# uart-opto-isolation.net
KiCad netlist of a schematic drawn in EAGLE
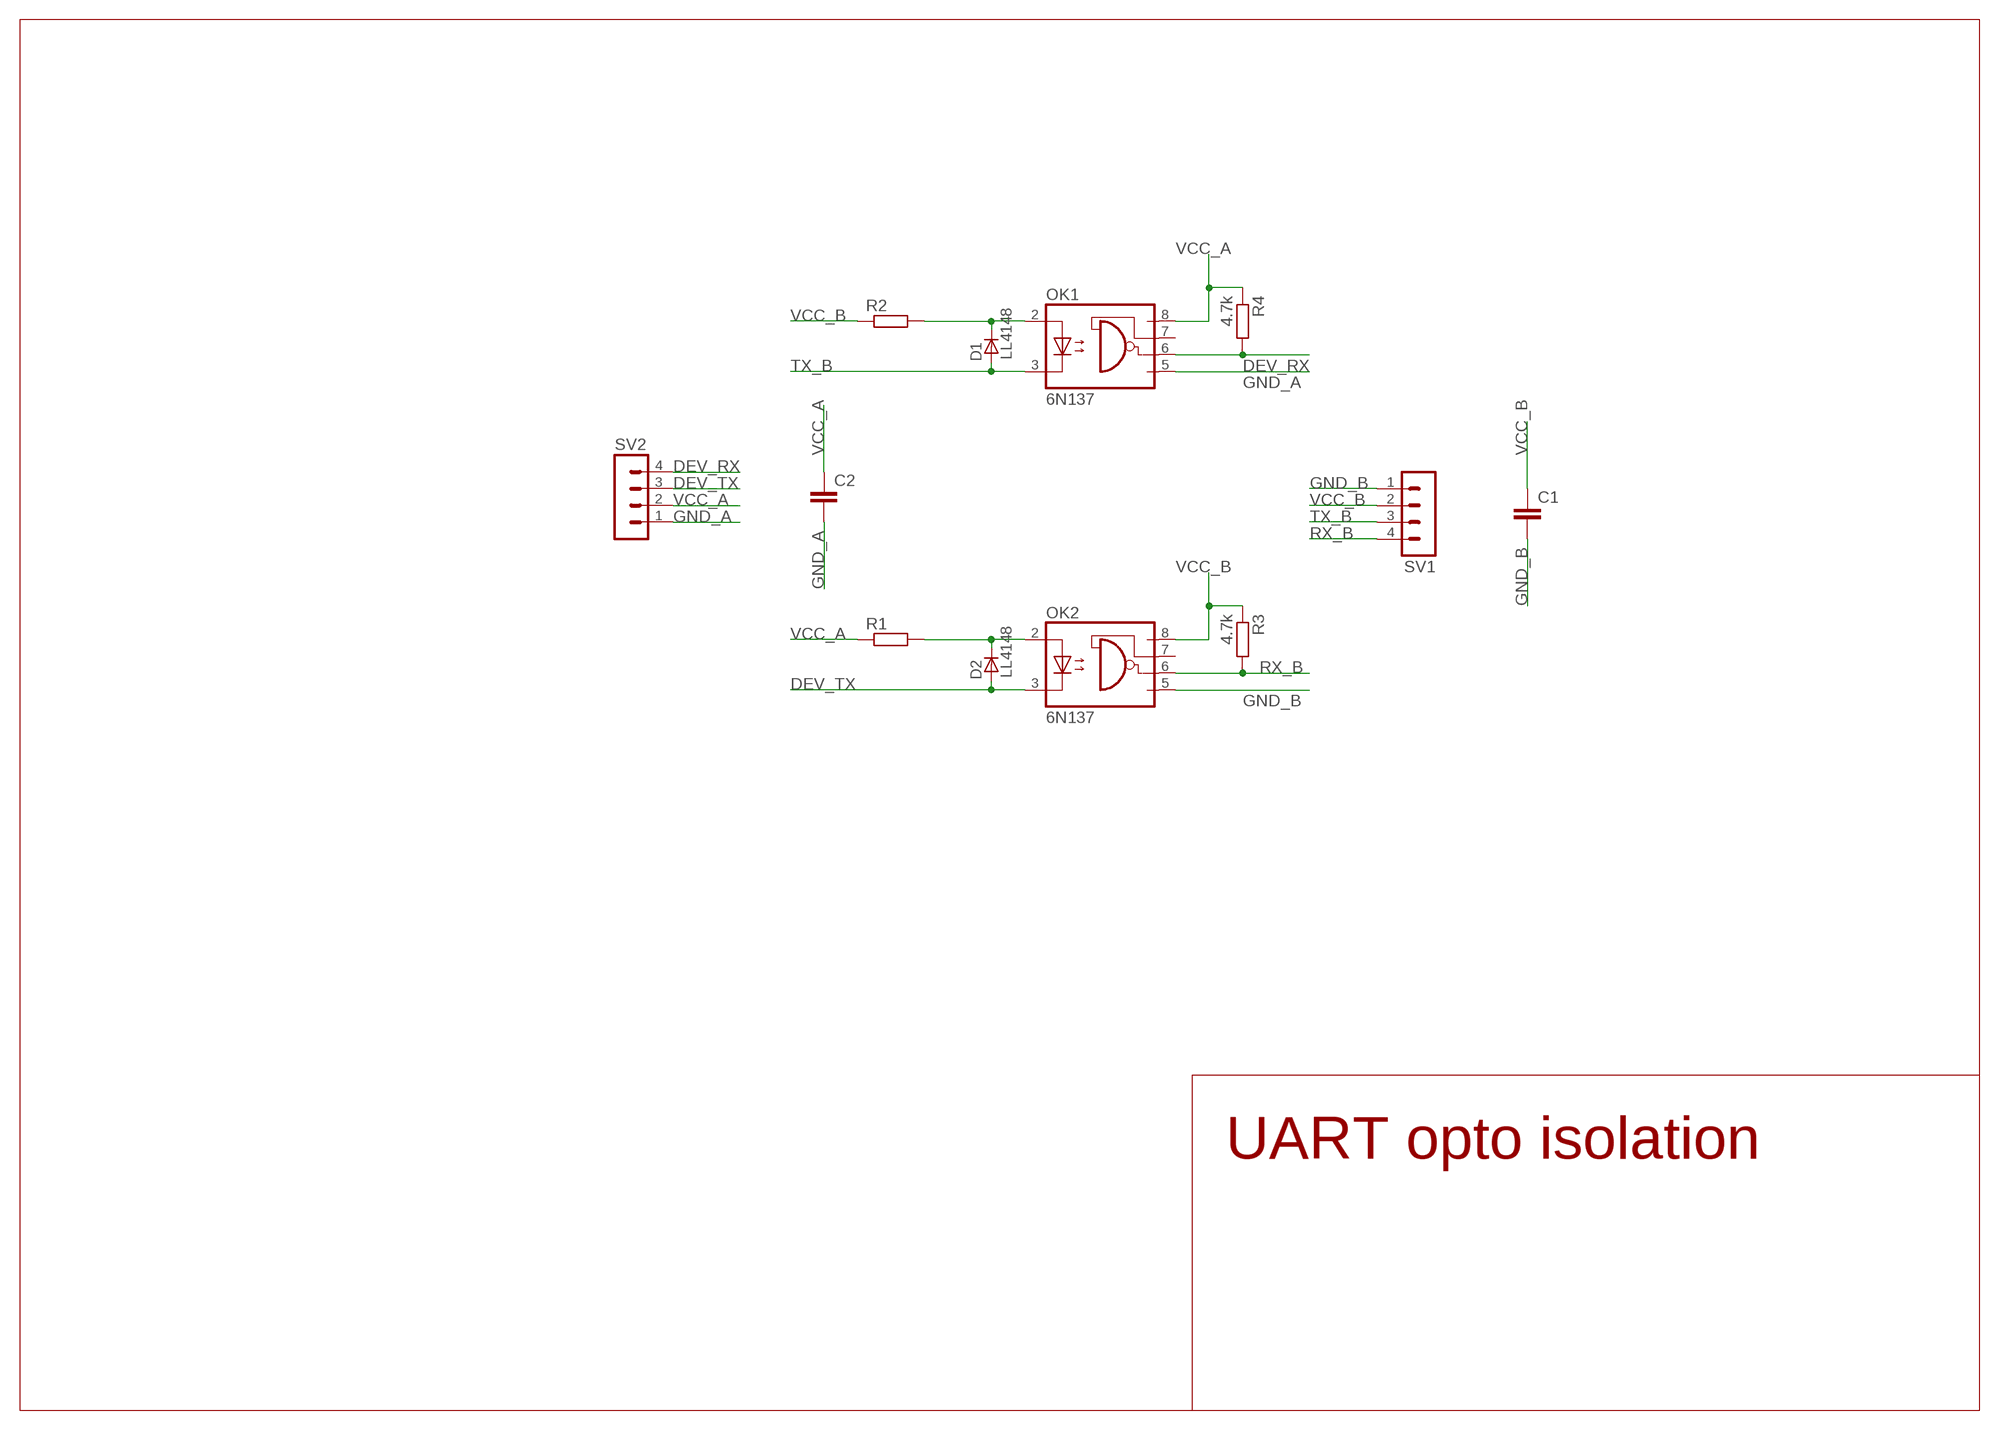
[diagram p0: schematic, sheet 1]
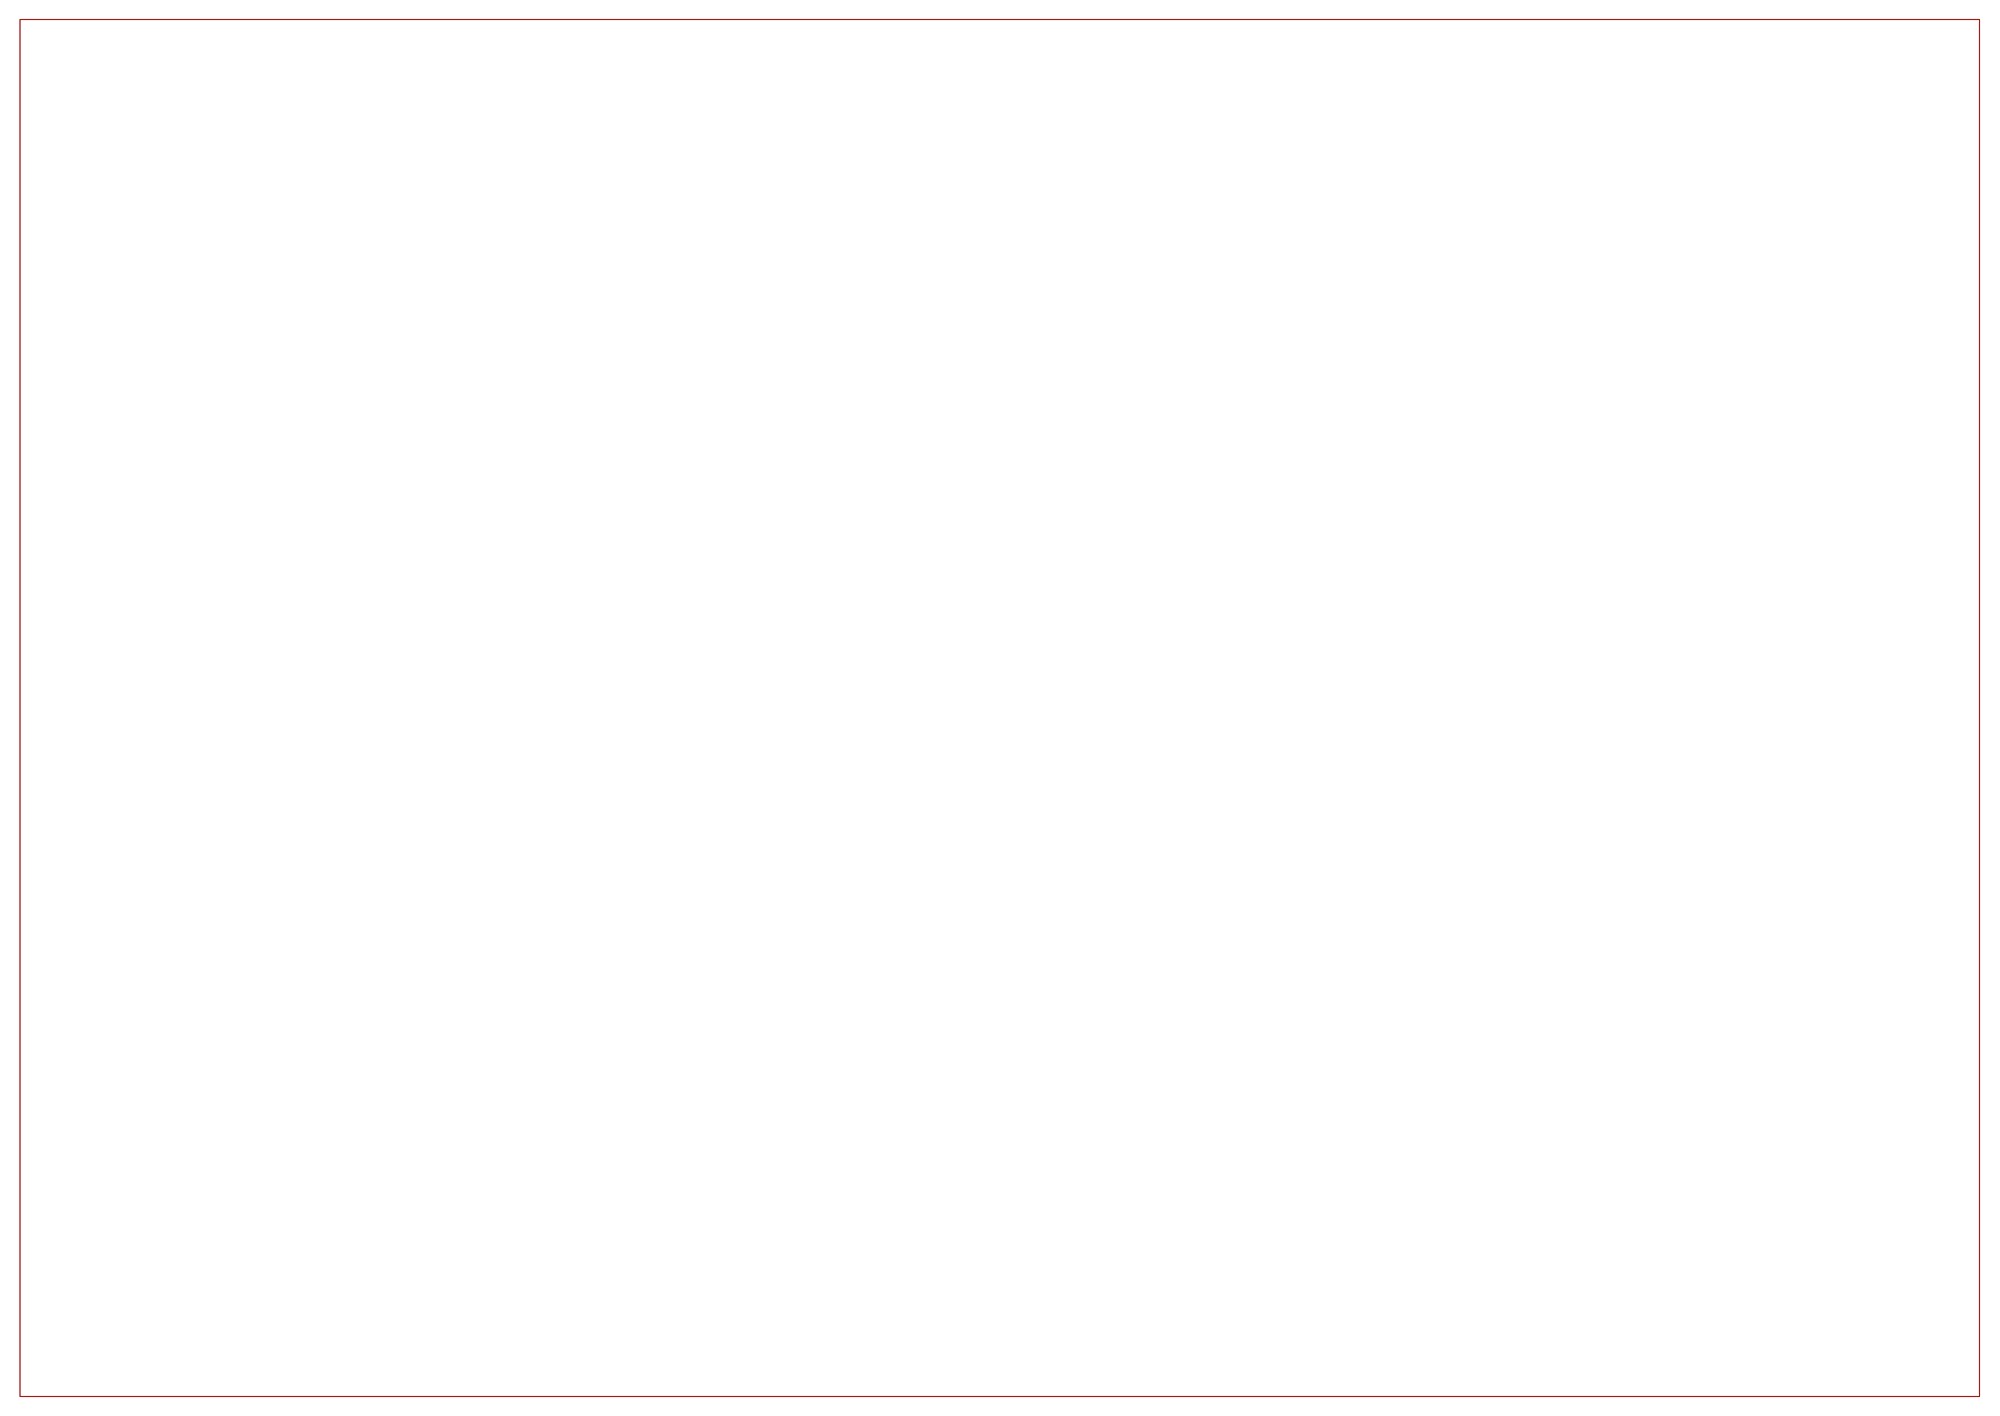
[diagram p1: schematic, sheet 2]

(export (version "E")
  (design (tool "Eeschema 10.0.6"))
  (components
    (comp (ref "C1")
      (value "C-EUC0805")
      (footprint "eagle-import:C0805")
      (libsource (lib "eagle-import") (part "C-EUC0805"))
    )
    (comp (ref "C2")
      (value "C-EUC0805")
      (footprint "eagle-import:C0805")
      (libsource (lib "eagle-import") (part "C-EUC0805"))
    )
    (comp (ref "D1")
      (value "LL4148")
      (footprint "eagle-import:SOD80_DO213AA_MINIMELF")
      (libsource (lib "eagle-import") (part "LL4148"))
    )
    (comp (ref "D2")
      (value "LL4148")
      (footprint "eagle-import:SOD80_DO213AA_MINIMELF")
      (libsource (lib "eagle-import") (part "LL4148"))
    )
    (comp (ref "OK1")
      (value "6N137")
      (footprint "eagle-import:DIL08")
      (libsource (lib "eagle-import") (part "6N137"))
    )
    (comp (ref "OK2")
      (value "6N137")
      (footprint "eagle-import:DIL08")
      (libsource (lib "eagle-import") (part "6N137"))
    )
    (comp (ref "R1")
      (value "R-EU_R0805")
      (footprint "eagle-import:R0805")
      (libsource (lib "eagle-import") (part "R-EU_R0805"))
    )
    (comp (ref "R2")
      (value "R-EU_R0805")
      (footprint "eagle-import:R0805")
      (libsource (lib "eagle-import") (part "R-EU_R0805"))
    )
    (comp (ref "R3")
      (value "4.7k")
      (footprint "eagle-import:R0805")
      (libsource (lib "eagle-import") (part "R-EU_R0805"))
    )
    (comp (ref "R4")
      (value "4.7k")
      (footprint "eagle-import:R0805")
      (libsource (lib "eagle-import") (part "R-EU_R0805"))
    )
    (comp (ref "SV1")
      (value "MA04-1")
      (footprint "eagle-import:MA04-1")
      (libsource (lib "eagle-import") (part "MA04-1"))
    )
    (comp (ref "SV2")
      (value "MA04-1")
      (footprint "eagle-import:MA04-1")
      (libsource (lib "eagle-import") (part "MA04-1"))
    )
  )
  (nets
    (net (code "1") (name "DEV_RX") (class "Default")
      (node (ref "OK1") (pin "6") (pinfunction "VO_6") (pintype "passive"))
      (node (ref "R4") (pin "2") (pinfunction "2_2") (pintype "passive"))
      (node (ref "SV2") (pin "4") (pinfunction "4_4") (pintype "passive"))
    )
    (net (code "2") (name "DEV_TX") (class "Default")
      (node (ref "D2") (pin "A") (pinfunction "A_A") (pintype "passive"))
      (node (ref "OK2") (pin "3") (pinfunction "C_3") (pintype "passive"))
      (node (ref "SV2") (pin "3") (pinfunction "3_3") (pintype "passive"))
    )
    (net (code "3") (name "GND_A") (class "Default")
      (node (ref "C2") (pin "2") (pinfunction "2_2") (pintype "passive"))
      (node (ref "OK1") (pin "5") (pinfunction "GND_5") (pintype "passive"))
      (node (ref "SV2") (pin "1") (pinfunction "1_1") (pintype "passive"))
    )
    (net (code "4") (name "GND_B") (class "Default")
      (node (ref "C1") (pin "2") (pinfunction "2_2") (pintype "passive"))
      (node (ref "OK2") (pin "5") (pinfunction "GND_5") (pintype "passive"))
      (node (ref "SV1") (pin "1") (pinfunction "1_1") (pintype "passive"))
    )
    (net (code "5") (name "Net-(OK1-A)") (class "Default")
      (node (ref "D1") (pin "C") (pinfunction "C_C") (pintype "passive"))
      (node (ref "OK1") (pin "2") (pinfunction "A_2") (pintype "passive"))
      (node (ref "R2") (pin "2") (pinfunction "2_2") (pintype "passive"))
    )
    (net (code "6") (name "Net-(OK2-A)") (class "Default")
      (node (ref "D2") (pin "C") (pinfunction "C_C") (pintype "passive"))
      (node (ref "OK2") (pin "2") (pinfunction "A_2") (pintype "passive"))
      (node (ref "R1") (pin "2") (pinfunction "2_2") (pintype "passive"))
    )
    (net (code "7") (name "RX_B") (class "Default")
      (node (ref "OK2") (pin "6") (pinfunction "VO_6") (pintype "passive"))
      (node (ref "R3") (pin "2") (pinfunction "2_2") (pintype "passive"))
      (node (ref "SV1") (pin "4") (pinfunction "4_4") (pintype "passive"))
    )
    (net (code "8") (name "TX_B") (class "Default")
      (node (ref "D1") (pin "A") (pinfunction "A_A") (pintype "passive"))
      (node (ref "OK1") (pin "3") (pinfunction "C_3") (pintype "passive"))
      (node (ref "SV1") (pin "3") (pinfunction "3_3") (pintype "passive"))
    )
    (net (code "9") (name "VCC_A") (class "Default")
      (node (ref "C2") (pin "1") (pinfunction "1_1") (pintype "passive"))
      (node (ref "OK1") (pin "8") (pinfunction "VCC_8") (pintype "passive"))
      (node (ref "R1") (pin "1") (pinfunction "1_1") (pintype "passive"))
      (node (ref "R4") (pin "1") (pinfunction "1_1") (pintype "passive"))
      (node (ref "SV2") (pin "2") (pinfunction "2_2") (pintype "passive"))
    )
    (net (code "10") (name "VCC_B") (class "Default")
      (node (ref "C1") (pin "1") (pinfunction "1_1") (pintype "passive"))
      (node (ref "OK2") (pin "8") (pinfunction "VCC_8") (pintype "passive"))
      (node (ref "R2") (pin "1") (pinfunction "1_1") (pintype "passive"))
      (node (ref "R3") (pin "1") (pinfunction "1_1") (pintype "passive"))
      (node (ref "SV1") (pin "2") (pinfunction "2_2") (pintype "passive"))
    )
    (net (code "11") (name "unconnected-(OK1-VE-Pad7)") (class "Default")
      (node (ref "OK1") (pin "7") (pinfunction "VE_7") (pintype "passive"))
    )
    (net (code "12") (name "unconnected-(OK2-VE-Pad7)") (class "Default")
      (node (ref "OK2") (pin "7") (pinfunction "VE_7") (pintype "passive"))
    )
  )
)
